# Connectors.net
KiCad netlist of a schematic drawn in Altium Designer
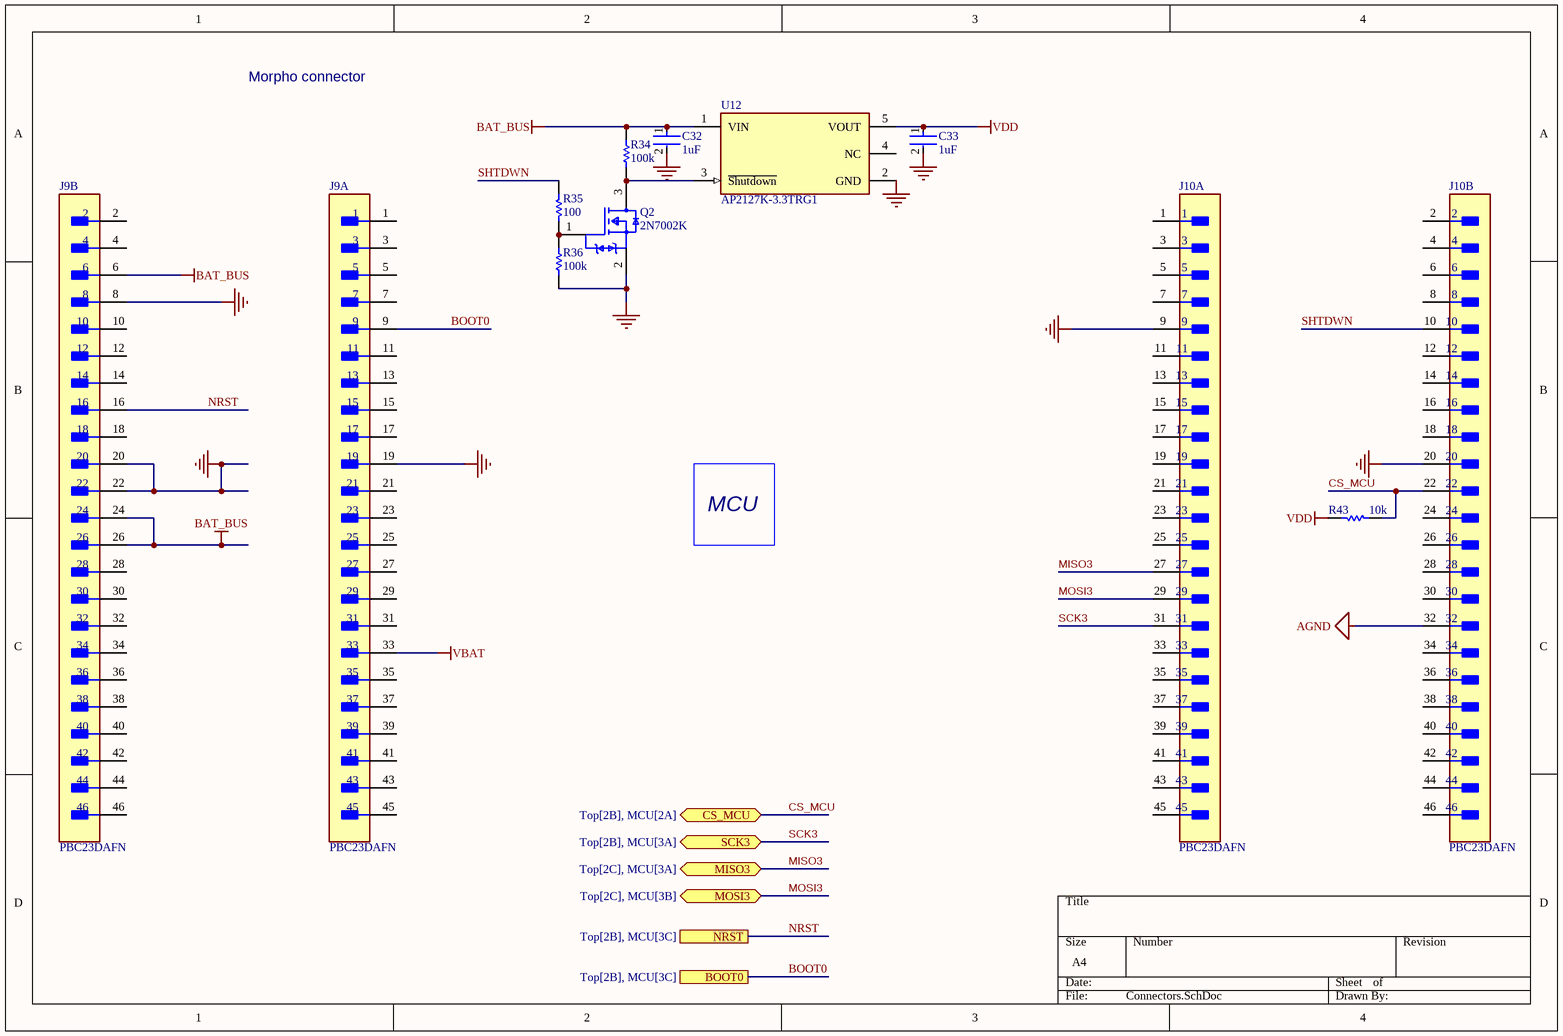
[diagram p0: Connectors.SchDoc]

(export (version "E")
  (design (tool "Eeschema 10.0.6"))
  (components
    (comp (ref "C32")
      (value "1uF")
      (footprint "FP-0603-L_1_6_0_15-W_0_81-IPC_B")
      (description "General Purpose Ceramic Capacitor, 0603, 1uF, 10%, X5R, 15%, 16V")
      (fields (field (name "VOLTAGE") "16V") (field (name "TOLERANCE") "10%"))
      (libsource (lib "Altium Content Vault") (part "02cd4be3c70576c341d710602a673aa"))
    )
    (comp (ref "C33")
      (value "1uF")
      (footprint "FP-0603-L_1_6_0_15-W_0_81-IPC_B")
      (description "General Purpose Ceramic Capacitor, 0603, 1uF, 10%, X5R, 15%, 16V")
      (fields (field (name "VOLTAGE") "16V") (field (name "TOLERANCE") "10%"))
      (libsource (lib "Altium Content Vault") (part "02cd4be3c70576c341d710602a673aa"))
    )
    (comp (ref "J9")
      (value "PBC23DAFN")
      (footprint "FP-PBC23DAFN-MFG")
      (description "CONN HEADER VERT 46POS 2.54MM")
      (libsource (lib "Altium Content Vault") (part "9d336348a4f8d78a7f3b81cc8d27765"))
    )
    (comp (ref "J10")
      (value "PBC23DAFN")
      (footprint "FP-PBC23DAFN-MFG")
      (description "CONN HEADER VERT 46POS 2.54MM")
      (libsource (lib "Altium Content Vault") (part "9d336348a4f8d78a7f3b81cc8d27765"))
    )
    (comp (ref "Q2")
      (value "2N7002K")
      (footprint "FP-318-08-MFG")
      (description "MOSFET N-CH 60V 300MA SOT23")
      (fields
        (field (name "OCTOPART") "https://octopart.com/2n7002k-on+semiconductor-84408900")
        (field (name "MANUFACTURER") "ON Semiconductor")
      )
      (libsource (lib "Altium Content Vault") (part "40bafa8609a25cdbb0dab398ef4a0d9"))
    )
    (comp (ref "R34")
      (value "100k")
      (footprint "RESC1005X40X25NL05T10")
      (fields (field (name "PART NUMBER") "RC0402FR-07100KL") (field (name "MANUFACTURER") "Yageo / Phycomp"))
      (libsource (lib "Altium Content Vault") (part "RES"))
    )
    (comp (ref "R35")
      (value "100")
      (footprint "RESC1608X55X30LL15T15")
      (fields (field (name "MANUFACTURER") "Panasonic") (field (name "PART NUMBER") "ERJ-3EKF1000V"))
      (libsource (lib "Altium Content Vault") (part "RES"))
    )
    (comp (ref "R36")
      (value "100k")
      (footprint "RESC1005X40X25NL05T10")
      (fields (field (name "PART NUMBER") "RC0402FR-07100KL") (field (name "MANUFACTURER") "Yageo / Phycomp"))
      (libsource (lib "Altium Content Vault") (part "RES"))
    )
    (comp (ref "R43")
      (value "10k")
      (footprint "RESC1005X40X25LL05T05")
      (description "Chip Resistor, 10 KOhm, +/- 1%, 0.1 W, -55 to 155 degC, 0402 (1005 Metric), RoHS, Tape and Reel")
      (fields (field (name "TOLERANCE") "1%") (field (name "MANUFACTURER") "Panasonic"))
      (libsource (lib "Altium Content Vault") (part "RES-2"))
    )
    (comp (ref "U12")
      (value "AP2127K-3.3TRG1")
      (footprint "FP-SOT25-MFG")
      (description "IC REG LINEAR 3.3V 300MA SOT23-5")
      (fields
        (field (name "MANUFACTURER") "Diodes Inc.")
        (field (name "OCTOPART") "https://octopart.com/ap2127k-3.3trg1-diodes+inc.-30954597")
      )
      (libsource (lib "Altium Content Vault") (part "9cec5dc8377dcc1fea4333fa34f1f58"))
    )
  )
  (nets
    (net (code "1") (name "/BOOT0") (class "Default")
      (node (ref "J9") (pin "9") (pinfunction "9_9") (pintype "passive"))
    )
    (net (code "2") (name "/CS_MCU") (class "Default")
      (node (ref "J10") (pin "22") (pinfunction "22_22") (pintype "passive"))
      (node (ref "R43") (pin "1") (pinfunction "1_1") (pintype "passive"))
    )
    (net (code "3") (name "/MISO3") (class "Default")
      (node (ref "J10") (pin "27") (pinfunction "27_27") (pintype "passive"))
    )
    (net (code "4") (name "/MOSI3") (class "Default")
      (node (ref "J10") (pin "29") (pinfunction "29_29") (pintype "passive"))
    )
    (net (code "5") (name "/NRST") (class "Default")
      (node (ref "J9") (pin "16") (pinfunction "16_16") (pintype "passive"))
    )
    (net (code "6") (name "/SCK3") (class "Default")
      (node (ref "J10") (pin "31") (pinfunction "31_31") (pintype "passive"))
    )
    (net (code "7") (name "/SHTDWN") (class "Default")
      (node (ref "J10") (pin "10") (pinfunction "10_10") (pintype "passive"))
      (node (ref "R35") (pin "2") (pinfunction "2_2") (pintype "passive"))
    )
    (net (code "8") (name "AGND") (class "Default")
      (node (ref "J10") (pin "32") (pinfunction "32_32") (pintype "passive"))
    )
    (net (code "9") (name "BAT_BUS") (class "Default")
      (node (ref "C32") (pin "1") (pinfunction "1_1") (pintype "passive"))
      (node (ref "J9") (pin "24") (pinfunction "24_24") (pintype "passive"))
      (node (ref "J9") (pin "26") (pinfunction "26_26") (pintype "passive"))
      (node (ref "J9") (pin "6") (pinfunction "6_6") (pintype "passive"))
      (node (ref "R34") (pin "2") (pinfunction "2_2") (pintype "passive"))
      (node (ref "U12") (pin "1") (pinfunction "VIN_1") (pintype "power_in"))
    )
    (net (code "10") (name "GND") (class "Default")
      (node (ref "C32") (pin "2") (pinfunction "2_2") (pintype "passive"))
      (node (ref "C33") (pin "2") (pinfunction "2_2") (pintype "passive"))
      (node (ref "J10") (pin "20") (pinfunction "20_20") (pintype "passive"))
      (node (ref "J10") (pin "9") (pinfunction "9_9") (pintype "passive"))
      (node (ref "J9") (pin "19") (pinfunction "19_19") (pintype "passive"))
      (node (ref "J9") (pin "20") (pinfunction "20_20") (pintype "passive"))
      (node (ref "J9") (pin "22") (pinfunction "22_22") (pintype "passive"))
      (node (ref "J9") (pin "8") (pinfunction "8_8") (pintype "passive"))
      (node (ref "Q2") (pin "2") (pinfunction "Source_2") (pintype "passive"))
      (node (ref "R36") (pin "1") (pinfunction "1_1") (pintype "passive"))
      (node (ref "U12") (pin "2") (pinfunction "GND_2") (pintype "power_in"))
    )
    (net (code "11") (name "Net-(Q2-Drain)") (class "Default")
      (node (ref "Q2") (pin "3") (pinfunction "Drain_3") (pintype "passive"))
      (node (ref "R34") (pin "1") (pinfunction "1_1") (pintype "passive"))
      (node (ref "U12") (pin "3") (pinfunction "~{Shutdown}_3") (pintype "input"))
    )
    (net (code "12") (name "Net-(Q2-Gate)") (class "Default")
      (node (ref "Q2") (pin "1") (pinfunction "Gate_1") (pintype "passive"))
      (node (ref "R35") (pin "1") (pinfunction "1_1") (pintype "passive"))
      (node (ref "R36") (pin "2") (pinfunction "2_2") (pintype "passive"))
    )
    (net (code "13") (name "VBAT") (class "Default")
      (node (ref "J9") (pin "33") (pinfunction "33_33") (pintype "passive"))
    )
    (net (code "14") (name "VDD") (class "Default")
      (node (ref "C33") (pin "1") (pinfunction "1_1") (pintype "passive"))
      (node (ref "R43") (pin "2") (pinfunction "2_2") (pintype "passive"))
      (node (ref "U12") (pin "5") (pinfunction "VOUT_5") (pintype "power_in"))
    )
    (net (code "15") (name "unconnected-(J9-Pad1)") (class "Default")
      (node (ref "J9") (pin "1") (pinfunction "1_1") (pintype "passive"))
    )
    (net (code "16") (name "unconnected-(J9-Pad2)") (class "Default")
      (node (ref "J9") (pin "2") (pinfunction "2_2") (pintype "passive"))
    )
    (net (code "17") (name "unconnected-(J9-Pad3)") (class "Default")
      (node (ref "J9") (pin "3") (pinfunction "3_3") (pintype "passive"))
    )
    (net (code "18") (name "unconnected-(J9-Pad4)") (class "Default")
      (node (ref "J9") (pin "4") (pinfunction "4_4") (pintype "passive"))
    )
    (net (code "19") (name "unconnected-(J9-Pad5)") (class "Default")
      (node (ref "J9") (pin "5") (pinfunction "5_5") (pintype "passive"))
    )
    (net (code "20") (name "unconnected-(J9-Pad7)") (class "Default")
      (node (ref "J9") (pin "7") (pinfunction "7_7") (pintype "passive"))
    )
    (net (code "21") (name "unconnected-(J9-Pad10)") (class "Default")
      (node (ref "J9") (pin "10") (pinfunction "10_10") (pintype "passive"))
    )
    (net (code "22") (name "unconnected-(J9-Pad11)") (class "Default")
      (node (ref "J9") (pin "11") (pinfunction "11_11") (pintype "passive"))
    )
    (net (code "23") (name "unconnected-(J9-Pad12)") (class "Default")
      (node (ref "J9") (pin "12") (pinfunction "12_12") (pintype "passive"))
    )
    (net (code "24") (name "unconnected-(J9-Pad13)") (class "Default")
      (node (ref "J9") (pin "13") (pinfunction "13_13") (pintype "passive"))
    )
    (net (code "25") (name "unconnected-(J9-Pad14)") (class "Default")
      (node (ref "J9") (pin "14") (pinfunction "14_14") (pintype "passive"))
    )
    (net (code "26") (name "unconnected-(J9-Pad15)") (class "Default")
      (node (ref "J9") (pin "15") (pinfunction "15_15") (pintype "passive"))
    )
    (net (code "27") (name "unconnected-(J9-Pad17)") (class "Default")
      (node (ref "J9") (pin "17") (pinfunction "17_17") (pintype "passive"))
    )
    (net (code "28") (name "unconnected-(J9-Pad18)") (class "Default")
      (node (ref "J9") (pin "18") (pinfunction "18_18") (pintype "passive"))
    )
    (net (code "29") (name "unconnected-(J9-Pad21)") (class "Default")
      (node (ref "J9") (pin "21") (pinfunction "21_21") (pintype "passive"))
    )
    (net (code "30") (name "unconnected-(J9-Pad23)") (class "Default")
      (node (ref "J9") (pin "23") (pinfunction "23_23") (pintype "passive"))
    )
    (net (code "31") (name "unconnected-(J9-Pad25)") (class "Default")
      (node (ref "J9") (pin "25") (pinfunction "25_25") (pintype "passive"))
    )
    (net (code "32") (name "unconnected-(J9-Pad27)") (class "Default")
      (node (ref "J9") (pin "27") (pinfunction "27_27") (pintype "passive"))
    )
    (net (code "33") (name "unconnected-(J9-Pad28)") (class "Default")
      (node (ref "J9") (pin "28") (pinfunction "28_28") (pintype "passive"))
    )
    (net (code "34") (name "unconnected-(J9-Pad29)") (class "Default")
      (node (ref "J9") (pin "29") (pinfunction "29_29") (pintype "passive"))
    )
    (net (code "35") (name "unconnected-(J9-Pad30)") (class "Default")
      (node (ref "J9") (pin "30") (pinfunction "30_30") (pintype "passive"))
    )
    (net (code "36") (name "unconnected-(J9-Pad31)") (class "Default")
      (node (ref "J9") (pin "31") (pinfunction "31_31") (pintype "passive"))
    )
    (net (code "37") (name "unconnected-(J9-Pad32)") (class "Default")
      (node (ref "J9") (pin "32") (pinfunction "32_32") (pintype "passive"))
    )
    (net (code "38") (name "unconnected-(J9-Pad34)") (class "Default")
      (node (ref "J9") (pin "34") (pinfunction "34_34") (pintype "passive"))
    )
    (net (code "39") (name "unconnected-(J9-Pad35)") (class "Default")
      (node (ref "J9") (pin "35") (pinfunction "35_35") (pintype "passive"))
    )
    (net (code "40") (name "unconnected-(J9-Pad36)") (class "Default")
      (node (ref "J9") (pin "36") (pinfunction "36_36") (pintype "passive"))
    )
    (net (code "41") (name "unconnected-(J9-Pad37)") (class "Default")
      (node (ref "J9") (pin "37") (pinfunction "37_37") (pintype "passive"))
    )
    (net (code "42") (name "unconnected-(J9-Pad38)") (class "Default")
      (node (ref "J9") (pin "38") (pinfunction "38_38") (pintype "passive"))
    )
    (net (code "43") (name "unconnected-(J9-Pad39)") (class "Default")
      (node (ref "J9") (pin "39") (pinfunction "39_39") (pintype "passive"))
    )
    (net (code "44") (name "unconnected-(J9-Pad40)") (class "Default")
      (node (ref "J9") (pin "40") (pinfunction "40_40") (pintype "passive"))
    )
    (net (code "45") (name "unconnected-(J9-Pad41)") (class "Default")
      (node (ref "J9") (pin "41") (pinfunction "41_41") (pintype "passive"))
    )
    (net (code "46") (name "unconnected-(J9-Pad42)") (class "Default")
      (node (ref "J9") (pin "42") (pinfunction "42_42") (pintype "passive"))
    )
    (net (code "47") (name "unconnected-(J9-Pad43)") (class "Default")
      (node (ref "J9") (pin "43") (pinfunction "43_43") (pintype "passive"))
    )
    (net (code "48") (name "unconnected-(J9-Pad44)") (class "Default")
      (node (ref "J9") (pin "44") (pinfunction "44_44") (pintype "passive"))
    )
    (net (code "49") (name "unconnected-(J9-Pad45)") (class "Default")
      (node (ref "J9") (pin "45") (pinfunction "45_45") (pintype "passive"))
    )
    (net (code "50") (name "unconnected-(J9-Pad46)") (class "Default")
      (node (ref "J9") (pin "46") (pinfunction "46_46") (pintype "passive"))
    )
    (net (code "51") (name "unconnected-(J10-Pad1)") (class "Default")
      (node (ref "J10") (pin "1") (pinfunction "1_1") (pintype "passive"))
    )
    (net (code "52") (name "unconnected-(J10-Pad2)") (class "Default")
      (node (ref "J10") (pin "2") (pinfunction "2_2") (pintype "passive"))
    )
    (net (code "53") (name "unconnected-(J10-Pad3)") (class "Default")
      (node (ref "J10") (pin "3") (pinfunction "3_3") (pintype "passive"))
    )
    (net (code "54") (name "unconnected-(J10-Pad4)") (class "Default")
      (node (ref "J10") (pin "4") (pinfunction "4_4") (pintype "passive"))
    )
    (net (code "55") (name "unconnected-(J10-Pad5)") (class "Default")
      (node (ref "J10") (pin "5") (pinfunction "5_5") (pintype "passive"))
    )
    (net (code "56") (name "unconnected-(J10-Pad6)") (class "Default")
      (node (ref "J10") (pin "6") (pinfunction "6_6") (pintype "passive"))
    )
    (net (code "57") (name "unconnected-(J10-Pad7)") (class "Default")
      (node (ref "J10") (pin "7") (pinfunction "7_7") (pintype "passive"))
    )
    (net (code "58") (name "unconnected-(J10-Pad8)") (class "Default")
      (node (ref "J10") (pin "8") (pinfunction "8_8") (pintype "passive"))
    )
    (net (code "59") (name "unconnected-(J10-Pad11)") (class "Default")
      (node (ref "J10") (pin "11") (pinfunction "11_11") (pintype "passive"))
    )
    (net (code "60") (name "unconnected-(J10-Pad12)") (class "Default")
      (node (ref "J10") (pin "12") (pinfunction "12_12") (pintype "passive"))
    )
    (net (code "61") (name "unconnected-(J10-Pad13)") (class "Default")
      (node (ref "J10") (pin "13") (pinfunction "13_13") (pintype "passive"))
    )
    (net (code "62") (name "unconnected-(J10-Pad14)") (class "Default")
      (node (ref "J10") (pin "14") (pinfunction "14_14") (pintype "passive"))
    )
    (net (code "63") (name "unconnected-(J10-Pad15)") (class "Default")
      (node (ref "J10") (pin "15") (pinfunction "15_15") (pintype "passive"))
    )
    (net (code "64") (name "unconnected-(J10-Pad16)") (class "Default")
      (node (ref "J10") (pin "16") (pinfunction "16_16") (pintype "passive"))
    )
    (net (code "65") (name "unconnected-(J10-Pad17)") (class "Default")
      (node (ref "J10") (pin "17") (pinfunction "17_17") (pintype "passive"))
    )
    (net (code "66") (name "unconnected-(J10-Pad18)") (class "Default")
      (node (ref "J10") (pin "18") (pinfunction "18_18") (pintype "passive"))
    )
    (net (code "67") (name "unconnected-(J10-Pad19)") (class "Default")
      (node (ref "J10") (pin "19") (pinfunction "19_19") (pintype "passive"))
    )
    (net (code "68") (name "unconnected-(J10-Pad21)") (class "Default")
      (node (ref "J10") (pin "21") (pinfunction "21_21") (pintype "passive"))
    )
    (net (code "69") (name "unconnected-(J10-Pad23)") (class "Default")
      (node (ref "J10") (pin "23") (pinfunction "23_23") (pintype "passive"))
    )
    (net (code "70") (name "unconnected-(J10-Pad24)") (class "Default")
      (node (ref "J10") (pin "24") (pinfunction "24_24") (pintype "passive"))
    )
    (net (code "71") (name "unconnected-(J10-Pad25)") (class "Default")
      (node (ref "J10") (pin "25") (pinfunction "25_25") (pintype "passive"))
    )
    (net (code "72") (name "unconnected-(J10-Pad26)") (class "Default")
      (node (ref "J10") (pin "26") (pinfunction "26_26") (pintype "passive"))
    )
    (net (code "73") (name "unconnected-(J10-Pad28)") (class "Default")
      (node (ref "J10") (pin "28") (pinfunction "28_28") (pintype "passive"))
    )
    (net (code "74") (name "unconnected-(J10-Pad30)") (class "Default")
      (node (ref "J10") (pin "30") (pinfunction "30_30") (pintype "passive"))
    )
    (net (code "75") (name "unconnected-(J10-Pad33)") (class "Default")
      (node (ref "J10") (pin "33") (pinfunction "33_33") (pintype "passive"))
    )
    (net (code "76") (name "unconnected-(J10-Pad34)") (class "Default")
      (node (ref "J10") (pin "34") (pinfunction "34_34") (pintype "passive"))
    )
    (net (code "77") (name "unconnected-(J10-Pad35)") (class "Default")
      (node (ref "J10") (pin "35") (pinfunction "35_35") (pintype "passive"))
    )
    (net (code "78") (name "unconnected-(J10-Pad36)") (class "Default")
      (node (ref "J10") (pin "36") (pinfunction "36_36") (pintype "passive"))
    )
    (net (code "79") (name "unconnected-(J10-Pad37)") (class "Default")
      (node (ref "J10") (pin "37") (pinfunction "37_37") (pintype "passive"))
    )
    (net (code "80") (name "unconnected-(J10-Pad38)") (class "Default")
      (node (ref "J10") (pin "38") (pinfunction "38_38") (pintype "passive"))
    )
    (net (code "81") (name "unconnected-(J10-Pad39)") (class "Default")
      (node (ref "J10") (pin "39") (pinfunction "39_39") (pintype "passive"))
    )
    (net (code "82") (name "unconnected-(J10-Pad40)") (class "Default")
      (node (ref "J10") (pin "40") (pinfunction "40_40") (pintype "passive"))
    )
    (net (code "83") (name "unconnected-(J10-Pad41)") (class "Default")
      (node (ref "J10") (pin "41") (pinfunction "41_41") (pintype "passive"))
    )
    (net (code "84") (name "unconnected-(J10-Pad42)") (class "Default")
      (node (ref "J10") (pin "42") (pinfunction "42_42") (pintype "passive"))
    )
    (net (code "85") (name "unconnected-(J10-Pad43)") (class "Default")
      (node (ref "J10") (pin "43") (pinfunction "43_43") (pintype "passive"))
    )
    (net (code "86") (name "unconnected-(J10-Pad44)") (class "Default")
      (node (ref "J10") (pin "44") (pinfunction "44_44") (pintype "passive"))
    )
    (net (code "87") (name "unconnected-(J10-Pad45)") (class "Default")
      (node (ref "J10") (pin "45") (pinfunction "45_45") (pintype "passive"))
    )
    (net (code "88") (name "unconnected-(J10-Pad46)") (class "Default")
      (node (ref "J10") (pin "46") (pinfunction "46_46") (pintype "passive"))
    )
    (net (code "89") (name "unconnected-(U12-NC-Pad4)") (class "Default")
      (node (ref "U12") (pin "4") (pinfunction "NC_4") (pintype "passive"))
    )
  )
)
